# Main_MCU.net
KiCad netlist of a schematic drawn in Altium Designer
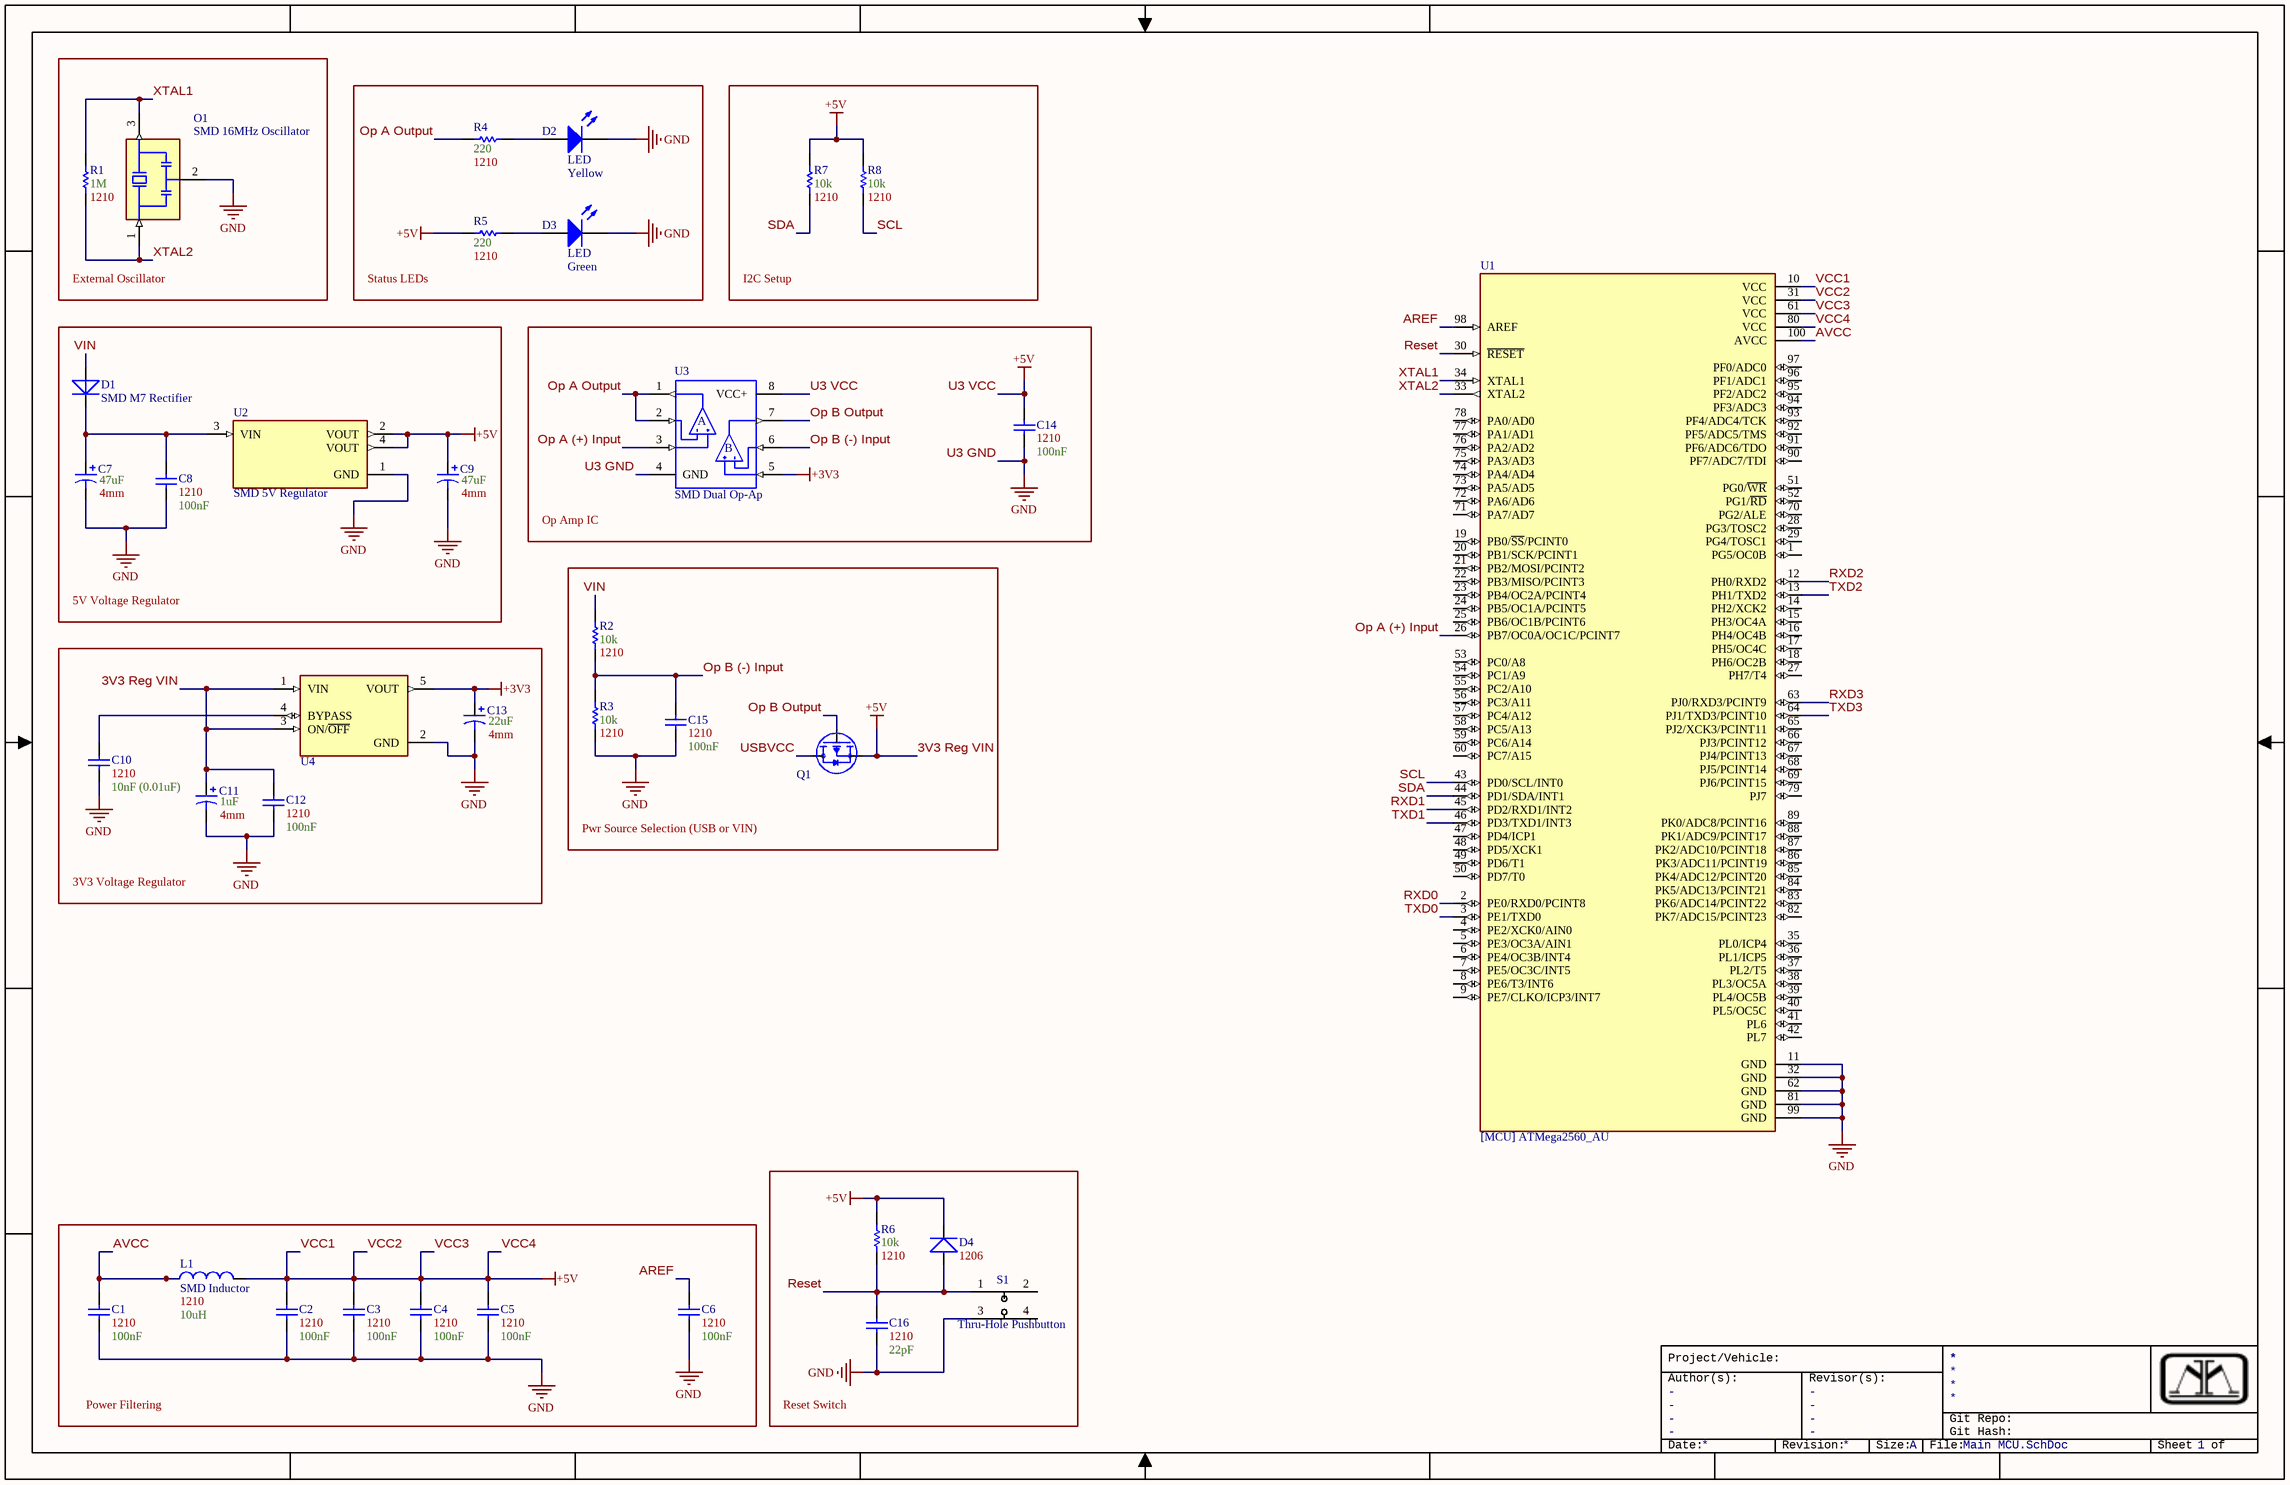
[diagram p0: Main MCU.SchDoc]

(export (version "E")
  (design (tool "Eeschema 10.0.6"))
  (components
    (comp (ref "C1")
      (value "SMD Capacitor")
      (footprint "SMD Capacitor [1210]")
      (fields
        (field (name "MOUSER PART #") "581-12107C104KAT2A")
        (field (name "SIZE PACKAGE") "1210")
        (field (name "CAPACITANCE") "100nF")
      )
      (libsource (lib "RADM Components") (part "SMD Capacitor"))
    )
    (comp (ref "C2")
      (value "SMD Capacitor")
      (footprint "SMD Capacitor [1210]")
      (fields
        (field (name "MOUSER PART #") "581-12107C104KAT2A")
        (field (name "SIZE PACKAGE") "1210")
        (field (name "CAPACITANCE") "100nF")
      )
      (libsource (lib "RADM Components") (part "SMD Capacitor"))
    )
    (comp (ref "C3")
      (value "SMD Capacitor")
      (footprint "SMD Capacitor [1210]")
      (fields
        (field (name "MOUSER PART #") "581-12107C104KAT2A")
        (field (name "SIZE PACKAGE") "1210")
        (field (name "CAPACITANCE") "100nF")
      )
      (libsource (lib "RADM Components") (part "SMD Capacitor"))
    )
    (comp (ref "C4")
      (value "SMD Capacitor")
      (footprint "SMD Capacitor [1210]")
      (fields
        (field (name "MOUSER PART #") "581-12107C104KAT2A")
        (field (name "SIZE PACKAGE") "1210")
        (field (name "CAPACITANCE") "100nF")
      )
      (libsource (lib "RADM Components") (part "SMD Capacitor"))
    )
    (comp (ref "C5")
      (value "SMD Capacitor")
      (footprint "SMD Capacitor [1210]")
      (fields
        (field (name "MOUSER PART #") "581-12107C104KAT2A")
        (field (name "SIZE PACKAGE") "1210")
        (field (name "CAPACITANCE") "100nF")
      )
      (libsource (lib "RADM Components") (part "SMD Capacitor"))
    )
    (comp (ref "C6")
      (value "SMD Capacitor")
      (footprint "SMD Capacitor [1210]")
      (fields
        (field (name "MOUSER PART #") "581-12107C104KAT2A")
        (field (name "SIZE PACKAGE") "1210")
        (field (name "CAPACITANCE") "100nF")
      )
      (libsource (lib "RADM Components") (part "SMD Capacitor"))
    )
    (comp (ref "C7")
      (value "SMD Cap - Polarized")
      (footprint "SMD Cap - Polarized, 4mm")
      (description "Diameter: 4mm")
      (fields
        (field (name "MOUSER PART #") "80-EDH476M6R3A9BAA")
        (field (name "CAPACITANCE") "47uF")
        (field (name "DIAMETER") "4mm")
      )
      (libsource (lib "RADM Components") (part "SMD Cap - Polarized"))
    )
    (comp (ref "C8")
      (value "SMD Capacitor")
      (footprint "SMD Capacitor [1210]")
      (fields
        (field (name "MOUSER PART #") "581-12107C104KAT2A")
        (field (name "SIZE PACKAGE") "1210")
        (field (name "CAPACITANCE") "100nF")
      )
      (libsource (lib "RADM Components") (part "SMD Capacitor"))
    )
    (comp (ref "C9")
      (value "SMD Cap - Polarized")
      (footprint "SMD Cap - Polarized, 4mm")
      (description "Diameter: 4mm")
      (fields
        (field (name "MOUSER PART #") "80-EDH476M6R3A9BAA")
        (field (name "CAPACITANCE") "47uF")
        (field (name "DIAMETER") "4mm")
      )
      (libsource (lib "RADM Components") (part "SMD Cap - Polarized"))
    )
    (comp (ref "C10")
      (value "SMD Capacitor")
      (footprint "SMD Capacitor [1210]")
      (fields
        (field (name "MOUSER PART #") "810-CGA6P1C0G3B103G2")
        (field (name "SIZE PACKAGE") "1210")
        (field (name "CAPACITANCE") "10nF (0.01uF)")
      )
      (libsource (lib "RADM Components") (part "SMD Capacitor"))
    )
    (comp (ref "C11")
      (value "SMD Cap - Polarized")
      (footprint "SMD Cap - Polarized, 4mm")
      (description "Diameter: 4mm")
      (fields
        (field (name "MOUSER PART #") "80-EXV105M050A9BAA")
        (field (name "CAPACITANCE") "1uF")
        (field (name "DIAMETER") "4mm")
      )
      (libsource (lib "RADM Components") (part "SMD Cap - Polarized"))
    )
    (comp (ref "C12")
      (value "SMD Capacitor")
      (footprint "SMD Capacitor [1210]")
      (fields
        (field (name "MOUSER PART #") "581-12107C104KAT2A")
        (field (name "SIZE PACKAGE") "1210")
        (field (name "CAPACITANCE") "100nF")
      )
      (libsource (lib "RADM Components") (part "SMD Capacitor"))
    )
    (comp (ref "C13")
      (value "SMD Cap - Polarized")
      (footprint "SMD Cap - Polarized, 4mm")
      (description "Diameter: 4mm")
      (fields
        (field (name "MOUSER PART #") "667-EEE-FN1C220R")
        (field (name "CAPACITANCE") "22uF")
        (field (name "DIAMETER") "4mm")
      )
      (libsource (lib "RADM Components") (part "SMD Cap - Polarized"))
    )
    (comp (ref "C14")
      (value "SMD Capacitor")
      (footprint "SMD Capacitor [1210]")
      (fields
        (field (name "MOUSER PART #") "581-12107C104KAT2A")
        (field (name "SIZE PACKAGE") "1210")
        (field (name "CAPACITANCE") "100nF")
      )
      (libsource (lib "RADM Components") (part "SMD Capacitor"))
    )
    (comp (ref "C15")
      (value "SMD Capacitor")
      (footprint "SMD Capacitor [1210]")
      (fields
        (field (name "MOUSER PART #") "581-12107C104KAT2A")
        (field (name "SIZE PACKAGE") "1210")
        (field (name "CAPACITANCE") "100nF")
      )
      (libsource (lib "RADM Components") (part "SMD Capacitor"))
    )
    (comp (ref "C16")
      (value "SMD Capacitor")
      (footprint "SMD Capacitor [1210]")
      (fields (field (name "SIZE PACKAGE") "1210") (field (name "CAPACITANCE") "22pF"))
      (libsource (lib "RADM Components") (part "SMD Capacitor"))
    )
    (comp (ref "D1")
      (value "SMD M7 Rectifier")
      (footprint "SMD M7 Rectifier")
      (description "JLC Part #: C95872")
      (fields (field (name "JLC PART #") "C95872"))
      (libsource (lib "RADM Components") (part "SMD M7 Rectifier"))
    )
    (comp (ref "D2")
      (value "LED")
      (footprint "Small Yellow LED")
      (description "3mm LED")
      (fields (field (name "COLOR") "Yellow"))
      (libsource (lib "RADM Components") (part "Small LED"))
    )
    (comp (ref "D3")
      (value "LED")
      (footprint "Small Green LED")
      (description "3mm LED")
      (fields (field (name "COLOR") "Green"))
      (libsource (lib "RADM Components") (part "Small LED"))
    )
    (comp (ref "D4")
      (value "SMD Diode")
      (footprint "SMD Diode [1206]")
      (description "Part #: CD1206-S01575\r\nJLC Part #: C75465")
      (fields (field (name "JLC PART #") "C75465") (field (name "SIZE PACKAGE") "1206"))
      (libsource (lib "RADM Components") (part "SMD Diode"))
    )
    (comp (ref "L1")
      (value "SMD Inductor")
      (footprint "SMD Inductor [0603]")
      (fields
        (field (name "MOUSER PART #") "963-LBC3225T100KR")
        (field (name "SIZE PACKAGE") "1210")
        (field (name "INDUCTANCE") "10uH")
      )
      (libsource (lib "RADM Components") (part "SMD Inductor"))
    )
    (comp (ref "O1")
      (value "SMD 16MHz Oscillator")
      (footprint "SMD 16MHz Oscillator [1]")
      (description "Part #: CSTNE16M0V530000R0\r\nJLC Part #: C341521")
      (fields (field (name "JLC PART #") "C341521"))
      (libsource (lib "RADM Components") (part "SMD 16MHz Oscillator [1]"))
    )
    (comp (ref "Q1")
      (value "SMD Mosfet (Part #: PMV48XP)")
      (footprint "SMD Mosfet (Part #: PMV48XP)")
      (description "JLC Part #: C2959854")
      (fields (field (name "JLC PART #") "C2959854"))
      (libsource (lib "RADM Components") (part "SMD Mosfet (Part #{colon} PMV48XP)"))
    )
    (comp (ref "R1")
      (value "SMD Resistor")
      (footprint "SMD Resistor [1210]")
      (description "JLC Part #: C728401\r\n(for 1M Ohm Res)")
      (fields
        (field (name "JLC PART #") "C728401")
        (field (name "MOUSER PART #") "71-CRCW12101M00FKEAH")
        (field (name "RESISTANCE") "1M")
        (field (name "SIZE PACKAGE") "1210")
      )
      (libsource (lib "RADM Components") (part "SMD Resistor"))
    )
    (comp (ref "R2")
      (value "SMD Resistor")
      (footprint "SMD Resistor [1210]")
      (description "JLC Part #: C728401\r\n(for 1M Ohm Res)")
      (fields
        (field (name "MOUSER PART #") "71-CRCW121010K0JNAIF")
        (field (name "RESISTANCE") "10k")
        (field (name "SIZE PACKAGE") "1210")
      )
      (libsource (lib "RADM Components") (part "SMD Resistor"))
    )
    (comp (ref "R3")
      (value "SMD Resistor")
      (footprint "SMD Resistor [1210]")
      (description "JLC Part #: C728401\r\n(for 1M Ohm Res)")
      (fields
        (field (name "MOUSER PART #") "71-CRCW121010K0JNAIF")
        (field (name "RESISTANCE") "10k")
        (field (name "SIZE PACKAGE") "1210")
      )
      (libsource (lib "RADM Components") (part "SMD Resistor"))
    )
    (comp (ref "R4")
      (value "SMD Resistor")
      (footprint "SMD Resistor [1210]")
      (description "JLC Part #: C728401\r\n(for 1M Ohm Res)")
      (fields
        (field (name "MOUSER PART #") "71-CRCW1210220RJNEAH")
        (field (name "RESISTANCE") "220")
        (field (name "SIZE PACKAGE") "1210")
      )
      (libsource (lib "RADM Components") (part "SMD Resistor"))
    )
    (comp (ref "R5")
      (value "SMD Resistor")
      (footprint "SMD Resistor [1210]")
      (description "JLC Part #: C728401\r\n(for 1M Ohm Res)")
      (fields
        (field (name "MOUSER PART #") "71-CRCW1210220RJNEAH")
        (field (name "RESISTANCE") "220")
        (field (name "SIZE PACKAGE") "1210")
      )
      (libsource (lib "RADM Components") (part "SMD Resistor"))
    )
    (comp (ref "R6")
      (value "SMD Resistor")
      (footprint "SMD Resistor [1210]")
      (description "JLC Part #: C728401\r\n(for 1M Ohm Res)")
      (fields
        (field (name "MOUSER PART #") "71-CRCW121010K0JNAIF")
        (field (name "RESISTANCE") "10k")
        (field (name "SIZE PACKAGE") "1210")
      )
      (libsource (lib "RADM Components") (part "SMD Resistor"))
    )
    (comp (ref "R7")
      (value "SMD Resistor")
      (footprint "SMD Resistor [1210]")
      (description "JLC Part #: C728401\r\n(for 1M Ohm Res)")
      (fields
        (field (name "MOUSER PART #") "71-CRCW121010K0JNAIF")
        (field (name "RESISTANCE") "10k")
        (field (name "SIZE PACKAGE") "1210")
      )
      (libsource (lib "RADM Components") (part "SMD Resistor"))
    )
    (comp (ref "R8")
      (value "SMD Resistor")
      (footprint "SMD Resistor [1210]")
      (description "JLC Part #: C728401\r\n(for 1M Ohm Res)")
      (fields
        (field (name "MOUSER PART #") "71-CRCW121010K0JNAIF")
        (field (name "RESISTANCE") "10k")
        (field (name "SIZE PACKAGE") "1210")
      )
      (libsource (lib "RADM Components") (part "SMD Resistor"))
    )
    (comp (ref "S1")
      (value "Thru-Hole Pushbutton")
      (footprint "Thru-Hole Pushbutton")
      (description "Tactile 4pin SPST Pushbutton\r\n(what I expect is a regular pushbutton)")
      (libsource (lib "RADM Components") (part "Thru-Hole Pushbutton"))
    )
    (comp (ref "U1")
      (value "[MCU] ATMega2560_AU")
      (footprint "SMD ATMega2560_AU")
      (description "JLC Part #: C22460")
      (fields (field (name "JLC PART #") "C22460"))
      (libsource (lib "RADM Components") (part "[MCU] ATMega2560_AU"))
    )
    (comp (ref "U2")
      (value "SMD 5V Regulator")
      (footprint "SMD 5V Regulator")
      (description "Part #: LD1117S50CTR\r\nJLC Part #: C81157")
      (fields (field (name "JLC PART #") "C81157"))
      (libsource (lib "RADM Components") (part "SMD 5V Regulator"))
    )
    (comp (ref "U3")
      (value "SMD Dual Op-Ap")
      (footprint "SMD Dual Op-Ap (LMV358IDGKR)")
      (description "Part #: LMV358IDGKR")
      (fields (field (name "JLC PART #") "C105242"))
      (libsource (lib "RADM Components") (part "SMD Dual Op-Ap"))
    )
    (comp (ref "U4")
      (value "SMD 3V3 Regulator")
      (footprint "SMD 3V3 Regulator")
      (description "Part #: LP2985-33DBVR\r\nJLC Part #: C95414")
      (fields (field (name "JLC PART #") "C95414") (field (name "MOUSER PART #") "595-LP2985-33DBVR"))
      (libsource (lib "RADM Components") (part "SMD 3V3 Regulator"))
    )
  )
  (nets
    (net (code "1") (name "+3V3") (class "Default")
      (node (ref "C13") (pin "1") (pinfunction "1_1") (pintype "passive"))
      (node (ref "U3") (pin "5") (pinfunction "2IN+_5") (pintype "input"))
      (node (ref "U4") (pin "5") (pinfunction "VOUT_5") (pintype "output"))
    )
    (net (code "2") (name "+5V") (class "Default")
      (node (ref "C11") (pin "1") (pinfunction "1_1") (pintype "passive"))
      (node (ref "C12") (pin "2") (pinfunction "2_2") (pintype "passive"))
      (node (ref "C14") (pin "2") (pinfunction "2_2") (pintype "passive"))
      (node (ref "C2") (pin "2") (pinfunction "2_2") (pintype "passive"))
      (node (ref "C3") (pin "2") (pinfunction "2_2") (pintype "passive"))
      (node (ref "C4") (pin "2") (pinfunction "2_2") (pintype "passive"))
      (node (ref "C5") (pin "2") (pinfunction "2_2") (pintype "passive"))
      (node (ref "C9") (pin "1") (pinfunction "1_1") (pintype "passive"))
      (node (ref "D4") (pin "C") (pinfunction "C_C") (pintype "power_in"))
      (node (ref "L1") (pin "2") (pinfunction "2_2") (pintype "passive"))
      (node (ref "Q1") (pin "2") (pinfunction "S_2") (pintype "passive"))
      (node (ref "R5") (pin "2") (pinfunction "2_2") (pintype "passive"))
      (node (ref "R6") (pin "2") (pinfunction "2_2") (pintype "passive"))
      (node (ref "R7") (pin "2") (pinfunction "2_2") (pintype "passive"))
      (node (ref "R8") (pin "2") (pinfunction "2_2") (pintype "passive"))
      (node (ref "U1") (pin "10") (pinfunction "VCC_10") (pintype "power_in"))
      (node (ref "U1") (pin "31") (pinfunction "VCC_31") (pintype "power_in"))
      (node (ref "U1") (pin "61") (pinfunction "VCC_61") (pintype "power_in"))
      (node (ref "U1") (pin "80") (pinfunction "VCC_80") (pintype "power_in"))
      (node (ref "U2") (pin "2") (pinfunction "VOUT_2") (pintype "output"))
      (node (ref "U2") (pin "4") (pinfunction "VOUT_4") (pintype "output"))
      (node (ref "U3") (pin "8") (pinfunction "VCC+_8") (pintype "power_in"))
      (node (ref "U4") (pin "1") (pinfunction "VIN_1") (pintype "input"))
      (node (ref "U4") (pin "3") (pinfunction "ON/~{OFF}_3") (pintype "input"))
    )
    (net (code "3") (name "/AREF") (class "Default")
      (node (ref "C6") (pin "2") (pinfunction "2_2") (pintype "passive"))
      (node (ref "U1") (pin "98") (pinfunction "AREF_98") (pintype "input"))
    )
    (net (code "4") (name "/AVCC") (class "Default")
      (node (ref "C1") (pin "2") (pinfunction "2_2") (pintype "passive"))
      (node (ref "L1") (pin "1") (pinfunction "1_1") (pintype "passive"))
      (node (ref "U1") (pin "100") (pinfunction "AVCC_100") (pintype "power_in"))
    )
    (net (code "5") (name "/Op A (+) Input") (class "Default")
      (node (ref "U1") (pin "26") (pinfunction "PB7/OC0A/OC1C/PCINT7_26") (pintype "bidirectional"))
      (node (ref "U3") (pin "3") (pinfunction "1IN+_3") (pintype "input"))
    )
    (net (code "6") (name "/Op A Output") (class "Default")
      (node (ref "R4") (pin "2") (pinfunction "2_2") (pintype "passive"))
      (node (ref "U3") (pin "1") (pinfunction "1OUT_1") (pintype "output"))
      (node (ref "U3") (pin "2") (pinfunction "1IN-_2") (pintype "input"))
    )
    (net (code "7") (name "/Op B (-) Input") (class "Default")
      (node (ref "C15") (pin "2") (pinfunction "2_2") (pintype "passive"))
      (node (ref "R2") (pin "1") (pinfunction "1_1") (pintype "passive"))
      (node (ref "R3") (pin "2") (pinfunction "2_2") (pintype "passive"))
      (node (ref "U3") (pin "6") (pinfunction "2IN-_6") (pintype "input"))
    )
    (net (code "8") (name "/Op B Output") (class "Default")
      (node (ref "Q1") (pin "1") (pinfunction "G_1") (pintype "passive"))
      (node (ref "U3") (pin "7") (pinfunction "2OUT_7") (pintype "output"))
    )
    (net (code "9") (name "/RXD0") (class "Default")
      (node (ref "U1") (pin "2") (pinfunction "PE0/RXD0/PCINT8_2") (pintype "bidirectional"))
    )
    (net (code "10") (name "/RXD1") (class "Default")
      (node (ref "U1") (pin "45") (pinfunction "PD2/RXD1/INT2_45") (pintype "bidirectional"))
    )
    (net (code "11") (name "/RXD2") (class "Default")
      (node (ref "U1") (pin "12") (pinfunction "PH0/RXD2_12") (pintype "bidirectional"))
    )
    (net (code "12") (name "/RXD3") (class "Default")
      (node (ref "U1") (pin "63") (pinfunction "PJ0/RXD3/PCINT9_63") (pintype "bidirectional"))
    )
    (net (code "13") (name "/Reset") (class "Default")
      (node (ref "C16") (pin "2") (pinfunction "2_2") (pintype "passive"))
      (node (ref "D4") (pin "A") (pinfunction "A_A") (pintype "power_in"))
      (node (ref "R6") (pin "1") (pinfunction "1_1") (pintype "passive"))
      (node (ref "S1") (pin "1") (pintype "power_in"))
      (node (ref "U1") (pin "30") (pinfunction "~{RESET}_30") (pintype "input"))
    )
    (net (code "14") (name "/SCL") (class "Default")
      (node (ref "R8") (pin "1") (pinfunction "1_1") (pintype "passive"))
      (node (ref "U1") (pin "43") (pinfunction "PD0/SCL/INT0_43") (pintype "bidirectional"))
    )
    (net (code "15") (name "/SDA") (class "Default")
      (node (ref "R7") (pin "1") (pinfunction "1_1") (pintype "passive"))
      (node (ref "U1") (pin "44") (pinfunction "PD1/SDA/INT1_44") (pintype "bidirectional"))
    )
    (net (code "16") (name "/TXD0") (class "Default")
      (node (ref "U1") (pin "3") (pinfunction "PE1/TXD0_3") (pintype "bidirectional"))
    )
    (net (code "17") (name "/TXD1") (class "Default")
      (node (ref "U1") (pin "46") (pinfunction "PD3/TXD1/INT3_46") (pintype "bidirectional"))
    )
    (net (code "18") (name "/TXD2") (class "Default")
      (node (ref "U1") (pin "13") (pinfunction "PH1/TXD2_13") (pintype "bidirectional"))
    )
    (net (code "19") (name "/TXD3") (class "Default")
      (node (ref "U1") (pin "64") (pinfunction "PJ1/TXD3/PCINT10_64") (pintype "bidirectional"))
    )
    (net (code "20") (name "/USBVCC") (class "Default")
      (node (ref "Q1") (pin "3") (pinfunction "D_3") (pintype "passive"))
    )
    (net (code "21") (name "/VIN") (class "Default")
      (node (ref "D1") (pin "A") (pinfunction "A_A") (pintype "power_in"))
      (node (ref "R2") (pin "2") (pinfunction "2_2") (pintype "passive"))
    )
    (net (code "22") (name "/XTAL1") (class "Default")
      (node (ref "O1") (pin "3") (pinfunction "OUT_3") (pintype "output"))
      (node (ref "R1") (pin "2") (pinfunction "2_2") (pintype "passive"))
      (node (ref "U1") (pin "34") (pinfunction "XTAL1_34") (pintype "input"))
    )
    (net (code "23") (name "/XTAL2") (class "Default")
      (node (ref "O1") (pin "1") (pinfunction "IN_1") (pintype "input"))
      (node (ref "R1") (pin "1") (pinfunction "1_1") (pintype "passive"))
      (node (ref "U1") (pin "33") (pinfunction "XTAL2_33") (pintype "output"))
    )
    (net (code "24") (name "GND") (class "Default")
      (node (ref "C1") (pin "1") (pinfunction "1_1") (pintype "passive"))
      (node (ref "C10") (pin "1") (pinfunction "1_1") (pintype "passive"))
      (node (ref "C11") (pin "2") (pinfunction "2_2") (pintype "passive"))
      (node (ref "C12") (pin "1") (pinfunction "1_1") (pintype "passive"))
      (node (ref "C13") (pin "2") (pinfunction "2_2") (pintype "passive"))
      (node (ref "C14") (pin "1") (pinfunction "1_1") (pintype "passive"))
      (node (ref "C15") (pin "1") (pinfunction "1_1") (pintype "passive"))
      (node (ref "C16") (pin "1") (pinfunction "1_1") (pintype "passive"))
      (node (ref "C2") (pin "1") (pinfunction "1_1") (pintype "passive"))
      (node (ref "C3") (pin "1") (pinfunction "1_1") (pintype "passive"))
      (node (ref "C4") (pin "1") (pinfunction "1_1") (pintype "passive"))
      (node (ref "C5") (pin "1") (pinfunction "1_1") (pintype "passive"))
      (node (ref "C6") (pin "1") (pinfunction "1_1") (pintype "passive"))
      (node (ref "C7") (pin "2") (pinfunction "2_2") (pintype "passive"))
      (node (ref "C8") (pin "1") (pinfunction "1_1") (pintype "passive"))
      (node (ref "C9") (pin "2") (pinfunction "2_2") (pintype "passive"))
      (node (ref "D2") (pin "2") (pinfunction "K_2") (pintype "passive"))
      (node (ref "D3") (pin "2") (pinfunction "K_2") (pintype "passive"))
      (node (ref "O1") (pin "2") (pinfunction "GND_2") (pintype "power_in"))
      (node (ref "R3") (pin "1") (pinfunction "1_1") (pintype "passive"))
      (node (ref "S1") (pin "3") (pintype "power_in"))
      (node (ref "U1") (pin "11") (pinfunction "GND_11") (pintype "power_in"))
      (node (ref "U1") (pin "32") (pinfunction "GND_32") (pintype "power_in"))
      (node (ref "U1") (pin "62") (pinfunction "GND_62") (pintype "power_in"))
      (node (ref "U1") (pin "81") (pinfunction "GND_81") (pintype "power_in"))
      (node (ref "U1") (pin "99") (pinfunction "GND_99") (pintype "power_in"))
      (node (ref "U2") (pin "1") (pinfunction "GND_1") (pintype "power_in"))
      (node (ref "U3") (pin "4") (pinfunction "GND_4") (pintype "power_in"))
      (node (ref "U4") (pin "2") (pinfunction "GND_2") (pintype "power_in"))
    )
    (net (code "25") (name "Net-(D2-A)") (class "Default")
      (node (ref "D2") (pin "1") (pinfunction "A_1") (pintype "passive"))
      (node (ref "R4") (pin "1") (pinfunction "1_1") (pintype "passive"))
    )
    (net (code "26") (name "Net-(D3-A)") (class "Default")
      (node (ref "D3") (pin "1") (pinfunction "A_1") (pintype "passive"))
      (node (ref "R5") (pin "1") (pinfunction "1_1") (pintype "passive"))
    )
    (net (code "27") (name "Net-(U2-VIN)") (class "Default")
      (node (ref "C7") (pin "1") (pinfunction "1_1") (pintype "passive"))
      (node (ref "C8") (pin "2") (pinfunction "2_2") (pintype "passive"))
      (node (ref "D1") (pin "C") (pinfunction "C_C") (pintype "power_in"))
      (node (ref "U2") (pin "3") (pinfunction "VIN_3") (pintype "input"))
    )
    (net (code "28") (name "Net-(U4-BYPASS)") (class "Default")
      (node (ref "C10") (pin "2") (pinfunction "2_2") (pintype "passive"))
      (node (ref "U4") (pin "4") (pinfunction "BYPASS_4") (pintype "bidirectional"))
    )
    (net (code "29") (name "unconnected-(S1-Pad2)") (class "Default")
      (node (ref "S1") (pin "2") (pintype "power_in"))
    )
    (net (code "30") (name "unconnected-(S1-Pad4)") (class "Default")
      (node (ref "S1") (pin "4") (pintype "power_in"))
    )
    (net (code "31") (name "unconnected-(U1-PA0{slash}AD0-Pad78)") (class "Default")
      (node (ref "U1") (pin "78") (pinfunction "PA0/AD0_78") (pintype "bidirectional"))
    )
    (net (code "32") (name "unconnected-(U1-PA1{slash}AD1-Pad77)") (class "Default")
      (node (ref "U1") (pin "77") (pinfunction "PA1/AD1_77") (pintype "bidirectional"))
    )
    (net (code "33") (name "unconnected-(U1-PA2{slash}AD2-Pad76)") (class "Default")
      (node (ref "U1") (pin "76") (pinfunction "PA2/AD2_76") (pintype "bidirectional"))
    )
    (net (code "34") (name "unconnected-(U1-PA3{slash}AD3-Pad75)") (class "Default")
      (node (ref "U1") (pin "75") (pinfunction "PA3/AD3_75") (pintype "bidirectional"))
    )
    (net (code "35") (name "unconnected-(U1-PA4{slash}AD4-Pad74)") (class "Default")
      (node (ref "U1") (pin "74") (pinfunction "PA4/AD4_74") (pintype "bidirectional"))
    )
    (net (code "36") (name "unconnected-(U1-PA5{slash}AD5-Pad73)") (class "Default")
      (node (ref "U1") (pin "73") (pinfunction "PA5/AD5_73") (pintype "bidirectional"))
    )
    (net (code "37") (name "unconnected-(U1-PA6{slash}AD6-Pad72)") (class "Default")
      (node (ref "U1") (pin "72") (pinfunction "PA6/AD6_72") (pintype "bidirectional"))
    )
    (net (code "38") (name "unconnected-(U1-PA7{slash}AD7-Pad71)") (class "Default")
      (node (ref "U1") (pin "71") (pinfunction "PA7/AD7_71") (pintype "bidirectional"))
    )
    (net (code "39") (name "unconnected-(U1-PB0{slash}~{SS}{slash}PCINT0-Pad19)") (class "Default")
      (node (ref "U1") (pin "19") (pinfunction "PB0/~{SS}/PCINT0_19") (pintype "bidirectional"))
    )
    (net (code "40") (name "unconnected-(U1-PB1{slash}SCK{slash}PCINT1-Pad20)") (class "Default")
      (node (ref "U1") (pin "20") (pinfunction "PB1/SCK/PCINT1_20") (pintype "bidirectional"))
    )
    (net (code "41") (name "unconnected-(U1-PB2{slash}MOSI{slash}PCINT2-Pad21)") (class "Default")
      (node (ref "U1") (pin "21") (pinfunction "PB2/MOSI/PCINT2_21") (pintype "bidirectional"))
    )
    (net (code "42") (name "unconnected-(U1-PB3{slash}MISO{slash}PCINT3-Pad22)") (class "Default")
      (node (ref "U1") (pin "22") (pinfunction "PB3/MISO/PCINT3_22") (pintype "bidirectional"))
    )
    (net (code "43") (name "unconnected-(U1-PB4{slash}OC2A{slash}PCINT4-Pad23)") (class "Default")
      (node (ref "U1") (pin "23") (pinfunction "PB4/OC2A/PCINT4_23") (pintype "bidirectional"))
    )
    (net (code "44") (name "unconnected-(U1-PB5{slash}OC1A{slash}PCINT5-Pad24)") (class "Default")
      (node (ref "U1") (pin "24") (pinfunction "PB5/OC1A/PCINT5_24") (pintype "bidirectional"))
    )
    (net (code "45") (name "unconnected-(U1-PB6{slash}OC1B{slash}PCINT6-Pad25)") (class "Default")
      (node (ref "U1") (pin "25") (pinfunction "PB6/OC1B/PCINT6_25") (pintype "bidirectional"))
    )
    (net (code "46") (name "unconnected-(U1-PC0{slash}A8-Pad53)") (class "Default")
      (node (ref "U1") (pin "53") (pinfunction "PC0/A8_53") (pintype "bidirectional"))
    )
    (net (code "47") (name "unconnected-(U1-PC1{slash}A9-Pad54)") (class "Default")
      (node (ref "U1") (pin "54") (pinfunction "PC1/A9_54") (pintype "bidirectional"))
    )
    (net (code "48") (name "unconnected-(U1-PC2{slash}A10-Pad55)") (class "Default")
      (node (ref "U1") (pin "55") (pinfunction "PC2/A10_55") (pintype "bidirectional"))
    )
    (net (code "49") (name "unconnected-(U1-PC3{slash}A11-Pad56)") (class "Default")
      (node (ref "U1") (pin "56") (pinfunction "PC3/A11_56") (pintype "bidirectional"))
    )
    (net (code "50") (name "unconnected-(U1-PC4{slash}A12-Pad57)") (class "Default")
      (node (ref "U1") (pin "57") (pinfunction "PC4/A12_57") (pintype "bidirectional"))
    )
    (net (code "51") (name "unconnected-(U1-PC5{slash}A13-Pad58)") (class "Default")
      (node (ref "U1") (pin "58") (pinfunction "PC5/A13_58") (pintype "bidirectional"))
    )
    (net (code "52") (name "unconnected-(U1-PC6{slash}A14-Pad59)") (class "Default")
      (node (ref "U1") (pin "59") (pinfunction "PC6/A14_59") (pintype "bidirectional"))
    )
    (net (code "53") (name "unconnected-(U1-PC7{slash}A15-Pad60)") (class "Default")
      (node (ref "U1") (pin "60") (pinfunction "PC7/A15_60") (pintype "bidirectional"))
    )
    (net (code "54") (name "unconnected-(U1-PD4{slash}ICP1-Pad47)") (class "Default")
      (node (ref "U1") (pin "47") (pinfunction "PD4/ICP1_47") (pintype "bidirectional"))
    )
    (net (code "55") (name "unconnected-(U1-PD5{slash}XCK1-Pad48)") (class "Default")
      (node (ref "U1") (pin "48") (pinfunction "PD5/XCK1_48") (pintype "bidirectional"))
    )
    (net (code "56") (name "unconnected-(U1-PD6{slash}T1-Pad49)") (class "Default")
      (node (ref "U1") (pin "49") (pinfunction "PD6/T1_49") (pintype "bidirectional"))
    )
    (net (code "57") (name "unconnected-(U1-PD7{slash}T0-Pad50)") (class "Default")
      (node (ref "U1") (pin "50") (pinfunction "PD7/T0_50") (pintype "bidirectional"))
    )
    (net (code "58") (name "unconnected-(U1-PE2{slash}XCK0{slash}AIN0-Pad4)") (class "Default")
      (node (ref "U1") (pin "4") (pinfunction "PE2/XCK0/AIN0_4") (pintype "bidirectional"))
    )
    (net (code "59") (name "unconnected-(U1-PE3{slash}OC3A{slash}AIN1-Pad5)") (class "Default")
      (node (ref "U1") (pin "5") (pinfunction "PE3/OC3A/AIN1_5") (pintype "bidirectional"))
    )
    (net (code "60") (name "unconnected-(U1-PE4{slash}OC3B{slash}INT4-Pad6)") (class "Default")
      (node (ref "U1") (pin "6") (pinfunction "PE4/OC3B/INT4_6") (pintype "bidirectional"))
    )
    (net (code "61") (name "unconnected-(U1-PE5{slash}OC3C{slash}INT5-Pad7)") (class "Default")
      (node (ref "U1") (pin "7") (pinfunction "PE5/OC3C/INT5_7") (pintype "bidirectional"))
    )
    (net (code "62") (name "unconnected-(U1-PE6{slash}T3{slash}INT6-Pad8)") (class "Default")
      (node (ref "U1") (pin "8") (pinfunction "PE6/T3/INT6_8") (pintype "bidirectional"))
    )
    (net (code "63") (name "unconnected-(U1-PE7{slash}CLKO{slash}ICP3{slash}INT7-Pad9)") (class "Default")
      (node (ref "U1") (pin "9") (pinfunction "PE7/CLKO/ICP3/INT7_9") (pintype "bidirectional"))
    )
    (net (code "64") (name "unconnected-(U1-PF0{slash}ADC0-Pad97)") (class "Default")
      (node (ref "U1") (pin "97") (pinfunction "PF0/ADC0_97") (pintype "bidirectional"))
    )
    (net (code "65") (name "unconnected-(U1-PF1{slash}ADC1-Pad96)") (class "Default")
      (node (ref "U1") (pin "96") (pinfunction "PF1/ADC1_96") (pintype "bidirectional"))
    )
    (net (code "66") (name "unconnected-(U1-PF2{slash}ADC2-Pad95)") (class "Default")
      (node (ref "U1") (pin "95") (pinfunction "PF2/ADC2_95") (pintype "bidirectional"))
    )
    (net (code "67") (name "unconnected-(U1-PF3{slash}ADC3-Pad94)") (class "Default")
      (node (ref "U1") (pin "94") (pinfunction "PF3/ADC3_94") (pintype "bidirectional"))
    )
    (net (code "68") (name "unconnected-(U1-PF4{slash}ADC4{slash}TCK-Pad93)") (class "Default")
      (node (ref "U1") (pin "93") (pinfunction "PF4/ADC4/TCK_93") (pintype "bidirectional"))
    )
    (net (code "69") (name "unconnected-(U1-PF5{slash}ADC5{slash}TMS-Pad92)") (class "Default")
      (node (ref "U1") (pin "92") (pinfunction "PF5/ADC5/TMS_92") (pintype "bidirectional"))
    )
    (net (code "70") (name "unconnected-(U1-PF6{slash}ADC6{slash}TDO-Pad91)") (class "Default")
      (node (ref "U1") (pin "91") (pinfunction "PF6/ADC6/TDO_91") (pintype "bidirectional"))
    )
    (net (code "71") (name "unconnected-(U1-PF7{slash}ADC7{slash}TDI-Pad90)") (class "Default")
      (node (ref "U1") (pin "90") (pinfunction "PF7/ADC7/TDI_90") (pintype "bidirectional"))
    )
    (net (code "72") (name "unconnected-(U1-PG0{slash}~{WR}-Pad51)") (class "Default")
      (node (ref "U1") (pin "51") (pinfunction "PG0/~{WR}_51") (pintype "bidirectional"))
    )
    (net (code "73") (name "unconnected-(U1-PG1{slash}~{RD}-Pad52)") (class "Default")
      (node (ref "U1") (pin "52") (pinfunction "PG1/~{RD}_52") (pintype "bidirectional"))
    )
    (net (code "74") (name "unconnected-(U1-PG2{slash}ALE-Pad70)") (class "Default")
      (node (ref "U1") (pin "70") (pinfunction "PG2/ALE_70") (pintype "bidirectional"))
    )
    (net (code "75") (name "unconnected-(U1-PG3{slash}TOSC2-Pad28)") (class "Default")
      (node (ref "U1") (pin "28") (pinfunction "PG3/TOSC2_28") (pintype "bidirectional"))
    )
    (net (code "76") (name "unconnected-(U1-PG4{slash}TOSC1-Pad29)") (class "Default")
      (node (ref "U1") (pin "29") (pinfunction "PG4/TOSC1_29") (pintype "bidirectional"))
    )
    (net (code "77") (name "unconnected-(U1-PG5{slash}OC0B-Pad1)") (class "Default")
      (node (ref "U1") (pin "1") (pinfunction "PG5/OC0B_1") (pintype "bidirectional"))
    )
    (net (code "78") (name "unconnected-(U1-PH2{slash}XCK2-Pad14)") (class "Default")
      (node (ref "U1") (pin "14") (pinfunction "PH2/XCK2_14") (pintype "bidirectional"))
    )
    (net (code "79") (name "unconnected-(U1-PH3{slash}OC4A-Pad15)") (class "Default")
      (node (ref "U1") (pin "15") (pinfunction "PH3/OC4A_15") (pintype "bidirectional"))
    )
    (net (code "80") (name "unconnected-(U1-PH4{slash}OC4B-Pad16)") (class "Default")
      (node (ref "U1") (pin "16") (pinfunction "PH4/OC4B_16") (pintype "bidirectional"))
    )
    (net (code "81") (name "unconnected-(U1-PH5{slash}OC4C-Pad17)") (class "Default")
      (node (ref "U1") (pin "17") (pinfunction "PH5/OC4C_17") (pintype "bidirectional"))
    )
    (net (code "82") (name "unconnected-(U1-PH6{slash}OC2B-Pad18)") (class "Default")
      (node (ref "U1") (pin "18") (pinfunction "PH6/OC2B_18") (pintype "bidirectional"))
    )
    (net (code "83") (name "unconnected-(U1-PH7{slash}T4-Pad27)") (class "Default")
      (node (ref "U1") (pin "27") (pinfunction "PH7/T4_27") (pintype "bidirectional"))
    )
    (net (code "84") (name "unconnected-(U1-PJ2{slash}XCK3{slash}PCINT11-Pad65)") (class "Default")
      (node (ref "U1") (pin "65") (pinfunction "PJ2/XCK3/PCINT11_65") (pintype "bidirectional"))
    )
    (net (code "85") (name "unconnected-(U1-PJ3{slash}PCINT12-Pad66)") (class "Default")
      (node (ref "U1") (pin "66") (pinfunction "PJ3/PCINT12_66") (pintype "bidirectional"))
    )
    (net (code "86") (name "unconnected-(U1-PJ4{slash}PCINT13-Pad67)") (class "Default")
      (node (ref "U1") (pin "67") (pinfunction "PJ4/PCINT13_67") (pintype "bidirectional"))
    )
    (net (code "87") (name "unconnected-(U1-PJ5{slash}PCINT14-Pad68)") (class "Default")
      (node (ref "U1") (pin "68") (pinfunction "PJ5/PCINT14_68") (pintype "bidirectional"))
    )
    (net (code "88") (name "unconnected-(U1-PJ6{slash}PCINT15-Pad69)") (class "Default")
      (node (ref "U1") (pin "69") (pinfunction "PJ6/PCINT15_69") (pintype "bidirectional"))
    )
    (net (code "89") (name "unconnected-(U1-PJ7-Pad79)") (class "Default")
      (node (ref "U1") (pin "79") (pinfunction "PJ7_79") (pintype "bidirectional"))
    )
    (net (code "90") (name "unconnected-(U1-PK0{slash}ADC8{slash}PCINT16-Pad89)") (class "Default")
      (node (ref "U1") (pin "89") (pinfunction "PK0/ADC8/PCINT16_89") (pintype "bidirectional"))
    )
    (net (code "91") (name "unconnected-(U1-PK1{slash}ADC9{slash}PCINT17-Pad88)") (class "Default")
      (node (ref "U1") (pin "88") (pinfunction "PK1/ADC9/PCINT17_88") (pintype "bidirectional"))
    )
    (net (code "92") (name "unconnected-(U1-PK2{slash}ADC10{slash}PCINT18-Pad87)") (class "Default")
      (node (ref "U1") (pin "87") (pinfunction "PK2/ADC10/PCINT18_87") (pintype "bidirectional"))
    )
    (net (code "93") (name "unconnected-(U1-PK3{slash}ADC11{slash}PCINT19-Pad86)") (class "Default")
      (node (ref "U1") (pin "86") (pinfunction "PK3/ADC11/PCINT19_86") (pintype "bidirectional"))
    )
    (net (code "94") (name "unconnected-(U1-PK4{slash}ADC12{slash}PCINT20-Pad85)") (class "Default")
      (node (ref "U1") (pin "85") (pinfunction "PK4/ADC12/PCINT20_85") (pintype "bidirectional"))
    )
    (net (code "95") (name "unconnected-(U1-PK5{slash}ADC13{slash}PCINT21-Pad84)") (class "Default")
      (node (ref "U1") (pin "84") (pinfunction "PK5/ADC13/PCINT21_84") (pintype "bidirectional"))
    )
    (net (code "96") (name "unconnected-(U1-PK6{slash}ADC14{slash}PCINT22-Pad83)") (class "Default")
      (node (ref "U1") (pin "83") (pinfunction "PK6/ADC14/PCINT22_83") (pintype "bidirectional"))
    )
    (net (code "97") (name "unconnected-(U1-PK7{slash}ADC15{slash}PCINT23-Pad82)") (class "Default")
      (node (ref "U1") (pin "82") (pinfunction "PK7/ADC15/PCINT23_82") (pintype "bidirectional"))
    )
    (net (code "98") (name "unconnected-(U1-PL0{slash}ICP4-Pad35)") (class "Default")
      (node (ref "U1") (pin "35") (pinfunction "PL0/ICP4_35") (pintype "bidirectional"))
    )
    (net (code "99") (name "unconnected-(U1-PL1{slash}ICP5-Pad36)") (class "Default")
      (node (ref "U1") (pin "36") (pinfunction "PL1/ICP5_36") (pintype "bidirectional"))
    )
    (net (code "100") (name "unconnected-(U1-PL2{slash}T5-Pad37)") (class "Default")
      (node (ref "U1") (pin "37") (pinfunction "PL2/T5_37") (pintype "bidirectional"))
    )
    (net (code "101") (name "unconnected-(U1-PL3{slash}OC5A-Pad38)") (class "Default")
      (node (ref "U1") (pin "38") (pinfunction "PL3/OC5A_38") (pintype "bidirectional"))
    )
    (net (code "102") (name "unconnected-(U1-PL4{slash}OC5B-Pad39)") (class "Default")
      (node (ref "U1") (pin "39") (pinfunction "PL4/OC5B_39") (pintype "bidirectional"))
    )
    (net (code "103") (name "unconnected-(U1-PL5{slash}OC5C-Pad40)") (class "Default")
      (node (ref "U1") (pin "40") (pinfunction "PL5/OC5C_40") (pintype "bidirectional"))
    )
    (net (code "104") (name "unconnected-(U1-PL6-Pad41)") (class "Default")
      (node (ref "U1") (pin "41") (pinfunction "PL6_41") (pintype "bidirectional"))
    )
    (net (code "105") (name "unconnected-(U1-PL7-Pad42)") (class "Default")
      (node (ref "U1") (pin "42") (pinfunction "PL7_42") (pintype "bidirectional"))
    )
  )
)
